# IRCHR_CTRL_J002942REVB.net
KiCad netlist of a schematic drawn in EAGLE
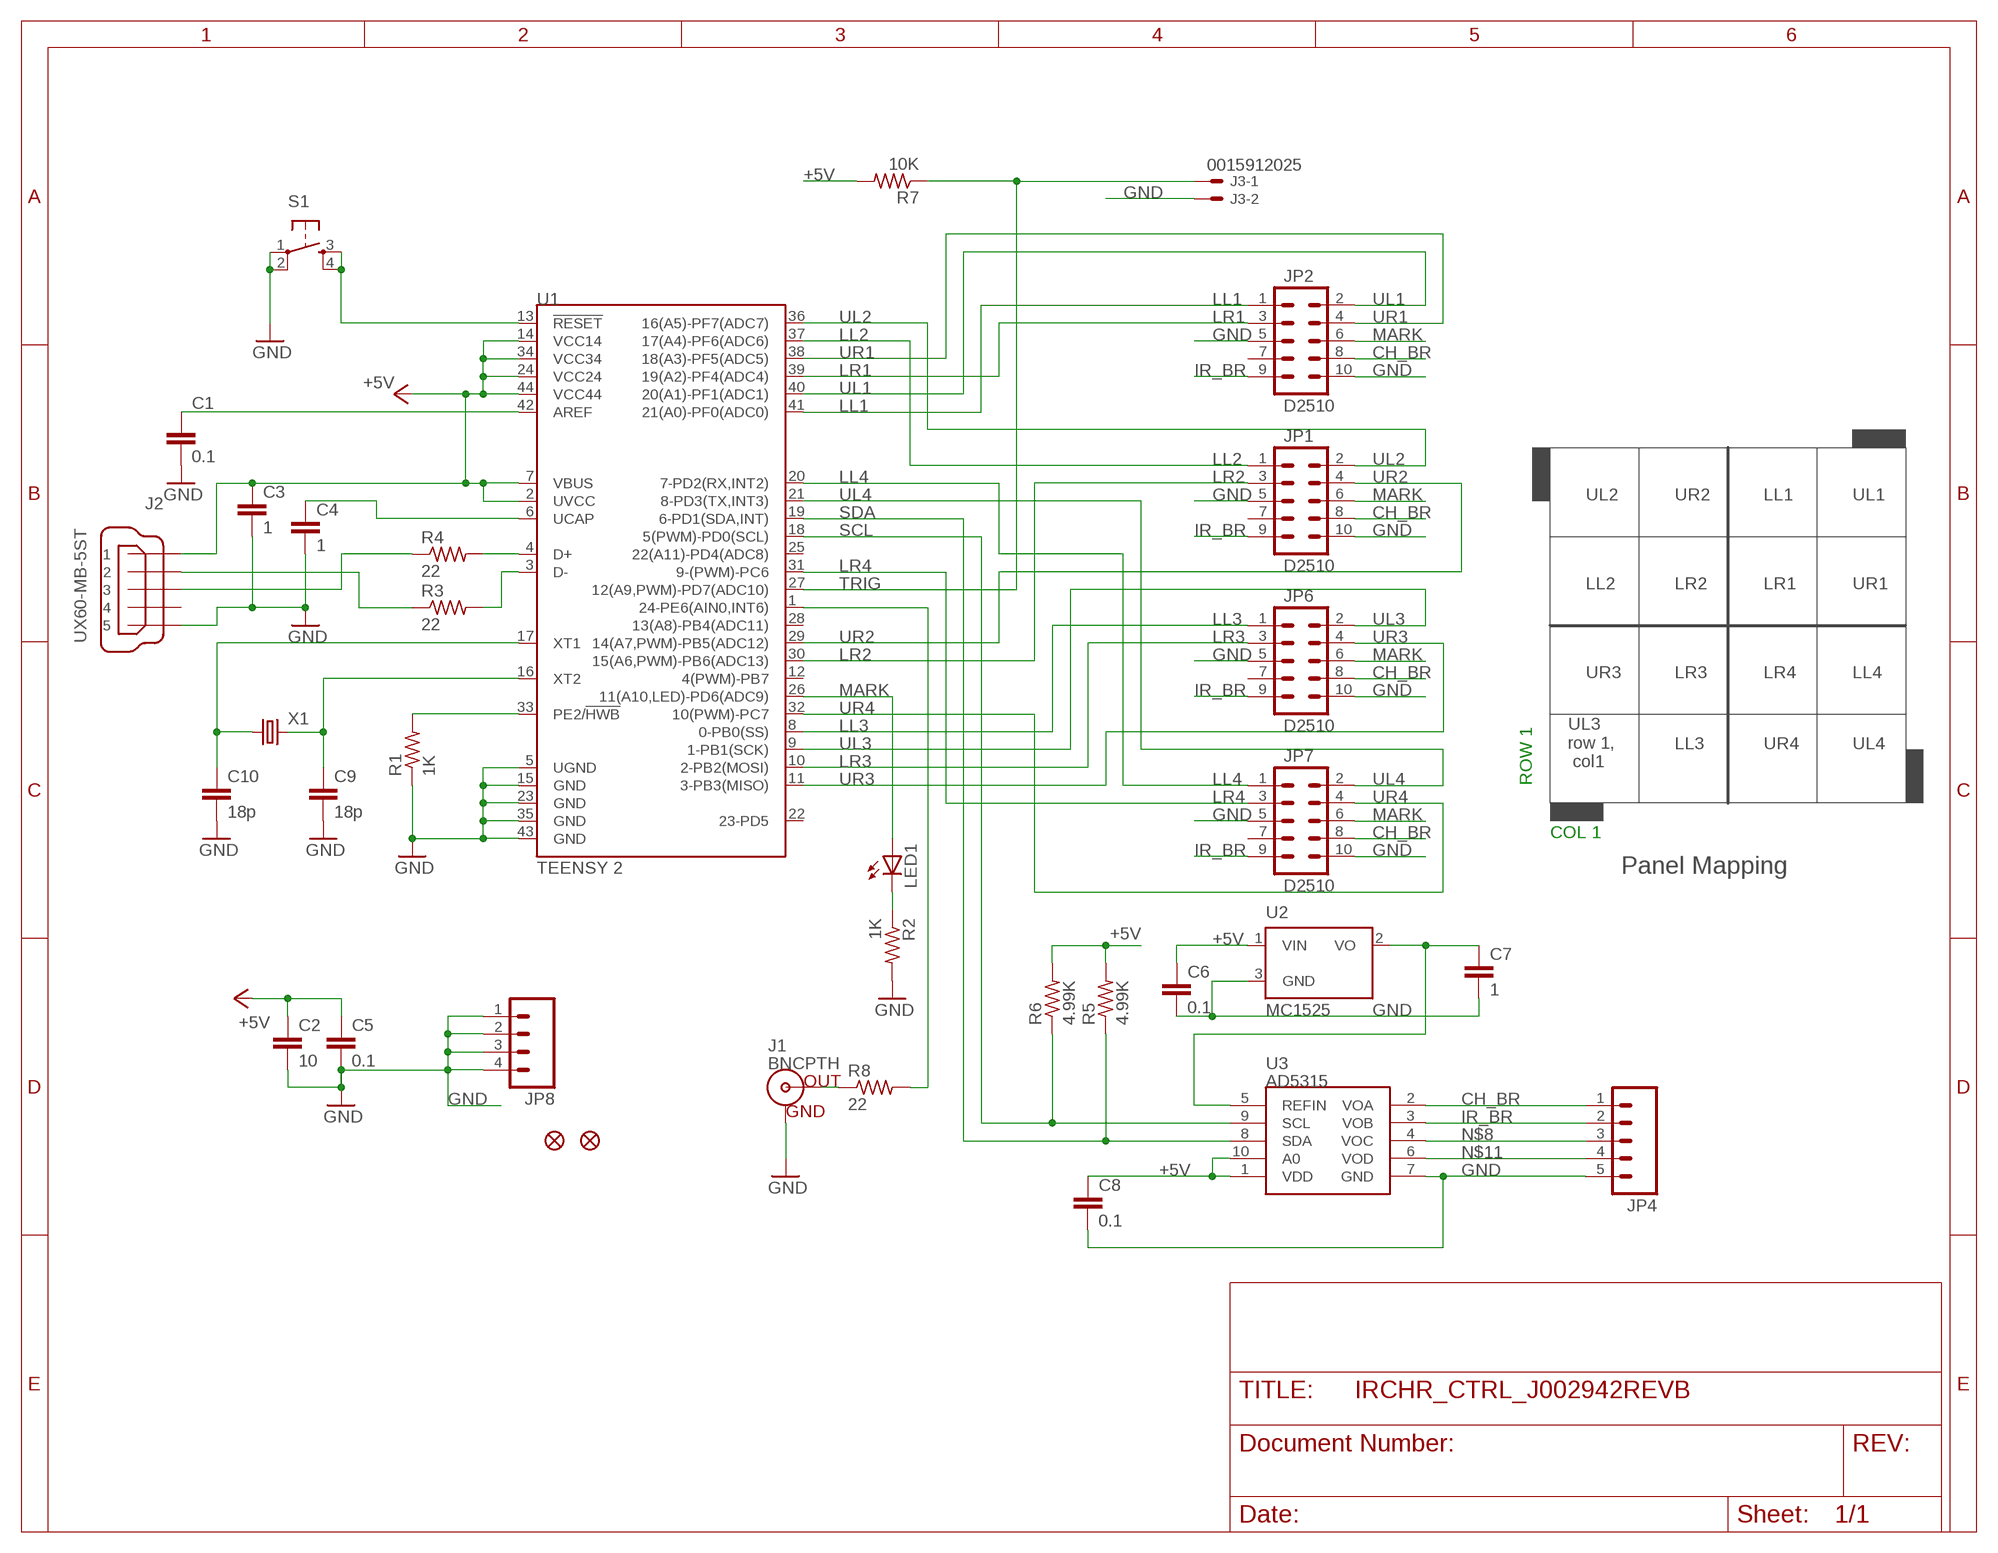
[diagram p0: schematic, sheet 1]

(export (version "E")
  (design (tool "Eeschema 10.0.6"))
  (components
    (comp (ref "C1")
      (value "0.1")
      (footprint "eagle-import:0805S")
      (libsource (lib "eagle-import") (part "STEVES_BU_CAPS0805S"))
    )
    (comp (ref "C2")
      (value "10")
      (footprint "eagle-import:1206S")
      (libsource (lib "eagle-import") (part "CAPS1206S"))
    )
    (comp (ref "C3")
      (value "1")
      (footprint "eagle-import:0805S")
      (libsource (lib "eagle-import") (part "STEVES_BU_CAPS0805S"))
    )
    (comp (ref "C4")
      (value "1")
      (footprint "eagle-import:0805S")
      (libsource (lib "eagle-import") (part "STEVES_BU_CAPS0805S"))
    )
    (comp (ref "C5")
      (value "0.1")
      (footprint "eagle-import:0805S")
      (libsource (lib "eagle-import") (part "STEVES_BU_CAPS0805S"))
    )
    (comp (ref "C6")
      (value "0.1")
      (footprint "eagle-import:0805S")
      (libsource (lib "eagle-import") (part "STEVES_BU_CAPS0805S"))
    )
    (comp (ref "C7")
      (value "1")
      (footprint "eagle-import:0805S")
      (libsource (lib "eagle-import") (part "STEVES_BU_CAPS0805S"))
    )
    (comp (ref "C8")
      (value "0.1")
      (footprint "eagle-import:0805S")
      (libsource (lib "eagle-import") (part "STEVES_BU_CAPS0805S"))
    )
    (comp (ref "C9")
      (value "18p")
      (footprint "eagle-import:0805S")
      (libsource (lib "eagle-import") (part "STEVES_BU_CAPS0805S"))
    )
    (comp (ref "C10")
      (value "18p")
      (footprint "eagle-import:0805S")
      (libsource (lib "eagle-import") (part "STEVES_BU_CAPS0805S"))
    )
    (comp (ref "J1")
      (value "BNCPTH")
      (footprint "eagle-import:BNC")
      (libsource (lib "eagle-import") (part "BNCPTH"))
    )
    (comp (ref "J2")
      (value "UX60-MB-5ST")
      (footprint "eagle-import:UX60-MB-5ST")
      (libsource (lib "eagle-import") (part "MINI-USB-UX60-MB-5ST"))
    )
    (comp (ref "J3")
      (value "0015912025")
      (footprint "eagle-import:15-91-02")
      (libsource (lib "eagle-import") (part "C-GRID-02-15-19"))
    )
    (comp (ref "JP1")
      (value "D2510")
      (footprint "eagle-import:2X5-SHROUDED_SMD_3M")
      (libsource (lib "eagle-import") (part "M05X22X5_SM_3M"))
    )
    (comp (ref "JP2")
      (value "D2510")
      (footprint "eagle-import:2X5-SHROUDED_SMD_3M")
      (libsource (lib "eagle-import") (part "M05X22X5_SM_3M"))
    )
    (comp (ref "JP3")
      (value "FIDUCIAL1X2.5")
      (footprint "eagle-import:FIDUCIAL-1X2.5")
      (libsource (lib "eagle-import") (part "FIDUCIAL1X2.5"))
    )
    (comp (ref "JP4")
      (value "M05LOCK")
      (footprint "eagle-import:1X05_LOCK")
      (libsource (lib "eagle-import") (part "M05LOCK"))
    )
    (comp (ref "JP5")
      (value "FIDUCIAL1X2.5")
      (footprint "eagle-import:FIDUCIAL-1X2.5")
      (libsource (lib "eagle-import") (part "FIDUCIAL1X2.5"))
    )
    (comp (ref "JP6")
      (value "D2510")
      (footprint "eagle-import:2X5-SHROUDED_SMD_3M")
      (libsource (lib "eagle-import") (part "M05X22X5_SM_3M"))
    )
    (comp (ref "JP7")
      (value "D2510")
      (footprint "eagle-import:2X5-SHROUDED_SMD_3M")
      (libsource (lib "eagle-import") (part "M05X22X5_SM_3M"))
    )
    (comp (ref "JP8")
      (value "M04LOCK")
      (footprint "eagle-import:1X04_LOCK")
      (libsource (lib "eagle-import") (part "M04LOCK"))
    )
    (comp (ref "LED1")
      (value "LEDCHIP-LED0805")
      (footprint "eagle-import:CHIP-LED0805")
      (libsource (lib "eagle-import") (part "LEDCHIP-LED0805"))
    )
    (comp (ref "R1")
      (value "1K")
      (footprint "eagle-import:0805S")
      (libsource (lib "eagle-import") (part "RESISTOR_SM0805S"))
    )
    (comp (ref "R2")
      (value "1K")
      (footprint "eagle-import:0805S")
      (libsource (lib "eagle-import") (part "RESISTOR_SM0805S"))
    )
    (comp (ref "R3")
      (value "22")
      (footprint "eagle-import:0805S")
      (libsource (lib "eagle-import") (part "RESISTOR_SM0805S"))
    )
    (comp (ref "R4")
      (value "22")
      (footprint "eagle-import:0805S")
      (libsource (lib "eagle-import") (part "RESISTOR_SM0805S"))
    )
    (comp (ref "R5")
      (value "4.99K")
      (footprint "eagle-import:0805S")
      (libsource (lib "eagle-import") (part "RESISTOR_SM0805S"))
    )
    (comp (ref "R6")
      (value "4.99K")
      (footprint "eagle-import:0805S")
      (libsource (lib "eagle-import") (part "RESISTOR_SM0805S"))
    )
    (comp (ref "R7")
      (value "10K")
      (footprint "eagle-import:0805S")
      (libsource (lib "eagle-import") (part "RESISTOR_SM0805S"))
    )
    (comp (ref "R8")
      (value "22")
      (footprint "eagle-import:0805S")
      (libsource (lib "eagle-import") (part "RESISTOR_SM0805S"))
    )
    (comp (ref "S1")
      (value "TAC_SWITCHSMD")
      (footprint "eagle-import:TACTILE_SWITCH_SMD")
      (libsource (lib "eagle-import") (part "TAC_SWITCHSMD"))
    )
    (comp (ref "U1")
      (value "TEENSY 2")
      (footprint "eagle-import:SPARKFUN-DIGITALIC_TQFP44")
      (libsource (lib "eagle-import") (part "TEENSY_CHIP"))
    )
    (comp (ref "U2")
      (value "MC1525")
      (footprint "eagle-import:SOT23")
      (libsource (lib "eagle-import") (part "MC15TT25"))
    )
    (comp (ref "U3")
      (value "AD5315")
      (footprint "eagle-import:MSOP10")
      (libsource (lib "eagle-import") (part "DAC_AD53X5"))
    )
    (comp (ref "X1")
      (value "CRYSTALCTS406")
      (footprint "eagle-import:CTS406")
      (libsource (lib "eagle-import") (part "CRYSTALCTS406"))
    )
  )
  (nets
    (net (code "1") (name "+5V") (class "Default")
      (node (ref "C2") (pin "1") (pinfunction "1_1") (pintype "passive"))
      (node (ref "C3") (pin "1") (pinfunction "1_1") (pintype "passive"))
      (node (ref "C5") (pin "1") (pinfunction "1_1") (pintype "passive"))
      (node (ref "C6") (pin "1") (pinfunction "1_1") (pintype "passive"))
      (node (ref "C8") (pin "1") (pinfunction "1_1") (pintype "passive"))
      (node (ref "J2") (pin "1") (pinfunction "1_1") (pintype "passive"))
      (node (ref "R5") (pin "2") (pinfunction "2_2") (pintype "passive"))
      (node (ref "R6") (pin "2") (pinfunction "2_2") (pintype "passive"))
      (node (ref "R7") (pin "2") (pinfunction "2_2") (pintype "passive"))
      (node (ref "U1") (pin "14") (pinfunction "VCC14_14") (pintype "bidirectional"))
      (node (ref "U1") (pin "2") (pinfunction "UVCC_2") (pintype "bidirectional"))
      (node (ref "U1") (pin "24") (pinfunction "VCC24_24") (pintype "bidirectional"))
      (node (ref "U1") (pin "34") (pinfunction "VCC34_34") (pintype "bidirectional"))
      (node (ref "U1") (pin "44") (pinfunction "VCC44_44") (pintype "bidirectional"))
      (node (ref "U1") (pin "7") (pinfunction "VBUS_7") (pintype "bidirectional"))
      (node (ref "U2") (pin "1") (pinfunction "VIN_1") (pintype "input"))
      (node (ref "U3") (pin "1") (pinfunction "VDD_1") (pintype "bidirectional"))
      (node (ref "U3") (pin "10") (pinfunction "A0_10") (pintype "bidirectional"))
    )
    (net (code "2") (name "/CH_BR") (class "Default")
      (node (ref "JP1") (pin "8") (pinfunction "8_8") (pintype "passive"))
      (node (ref "JP2") (pin "8") (pinfunction "8_8") (pintype "passive"))
      (node (ref "JP4") (pin "1") (pinfunction "1_1") (pintype "passive"))
      (node (ref "JP6") (pin "8") (pinfunction "8_8") (pintype "passive"))
      (node (ref "JP7") (pin "8") (pinfunction "8_8") (pintype "passive"))
      (node (ref "U3") (pin "2") (pinfunction "VOA_2") (pintype "bidirectional"))
    )
    (net (code "3") (name "/IR_BR") (class "Default")
      (node (ref "JP1") (pin "9") (pinfunction "9_9") (pintype "passive"))
      (node (ref "JP2") (pin "9") (pinfunction "9_9") (pintype "passive"))
      (node (ref "JP4") (pin "2") (pinfunction "2_2") (pintype "passive"))
      (node (ref "JP6") (pin "9") (pinfunction "9_9") (pintype "passive"))
      (node (ref "JP7") (pin "9") (pinfunction "9_9") (pintype "passive"))
      (node (ref "U3") (pin "3") (pinfunction "VOB_3") (pintype "bidirectional"))
    )
    (net (code "4") (name "/LL1") (class "Default")
      (node (ref "JP2") (pin "1") (pinfunction "1_1") (pintype "passive"))
      (node (ref "U1") (pin "41") (pinfunction "21(A0)-PF0(ADC0)_41") (pintype "bidirectional"))
    )
    (net (code "5") (name "/LL2") (class "Default")
      (node (ref "JP1") (pin "1") (pinfunction "1_1") (pintype "passive"))
      (node (ref "U1") (pin "37") (pinfunction "17(A4)-PF6(ADC6)_37") (pintype "bidirectional"))
    )
    (net (code "6") (name "/LL3") (class "Default")
      (node (ref "JP6") (pin "1") (pinfunction "1_1") (pintype "passive"))
      (node (ref "U1") (pin "8") (pinfunction "0-PB0(SS)_8") (pintype "bidirectional"))
    )
    (net (code "7") (name "/LL4") (class "Default")
      (node (ref "JP7") (pin "1") (pinfunction "1_1") (pintype "passive"))
      (node (ref "U1") (pin "20") (pinfunction "7-PD2(RX,INT2)_20") (pintype "bidirectional"))
    )
    (net (code "8") (name "/LR1") (class "Default")
      (node (ref "JP2") (pin "3") (pinfunction "3_3") (pintype "passive"))
      (node (ref "U1") (pin "39") (pinfunction "19(A2)-PF4(ADC4)_39") (pintype "bidirectional"))
    )
    (net (code "9") (name "/LR2") (class "Default")
      (node (ref "JP1") (pin "3") (pinfunction "3_3") (pintype "passive"))
      (node (ref "U1") (pin "30") (pinfunction "15(A6,PWM)-PB6(ADC13)_30") (pintype "bidirectional"))
    )
    (net (code "10") (name "/LR3") (class "Default")
      (node (ref "JP6") (pin "3") (pinfunction "3_3") (pintype "passive"))
      (node (ref "U1") (pin "10") (pinfunction "2-PB2(MOSI)_10") (pintype "bidirectional"))
    )
    (net (code "11") (name "/LR4") (class "Default")
      (node (ref "JP7") (pin "3") (pinfunction "3_3") (pintype "passive"))
      (node (ref "U1") (pin "31") (pinfunction "9-(PWM)-PC6_31") (pintype "bidirectional"))
    )
    (net (code "12") (name "/MARK") (class "Default")
      (node (ref "JP1") (pin "6") (pinfunction "6_6") (pintype "passive"))
      (node (ref "JP2") (pin "6") (pinfunction "6_6") (pintype "passive"))
      (node (ref "JP6") (pin "6") (pinfunction "6_6") (pintype "passive"))
      (node (ref "JP7") (pin "6") (pinfunction "6_6") (pintype "passive"))
      (node (ref "LED1") (pin "A") (pinfunction "A_A") (pintype "passive"))
      (node (ref "U1") (pin "26") (pinfunction "11(A10,LED)-PD6(ADC9)_26") (pintype "bidirectional"))
    )
    (net (code "13") (name "/N$8") (class "Default")
      (node (ref "JP4") (pin "3") (pinfunction "3_3") (pintype "passive"))
      (node (ref "U3") (pin "4") (pinfunction "VOC_4") (pintype "bidirectional"))
    )
    (net (code "14") (name "/N$11") (class "Default")
      (node (ref "JP4") (pin "4") (pinfunction "4_4") (pintype "passive"))
      (node (ref "U3") (pin "6") (pinfunction "VOD_6") (pintype "bidirectional"))
    )
    (net (code "15") (name "/SCL") (class "Default")
      (node (ref "R6") (pin "1") (pinfunction "1_1") (pintype "passive"))
      (node (ref "U1") (pin "18") (pinfunction "5(PWM)-PD0(SCL)_18") (pintype "bidirectional"))
      (node (ref "U3") (pin "9") (pinfunction "SCL_9") (pintype "bidirectional"))
    )
    (net (code "16") (name "/SDA") (class "Default")
      (node (ref "R5") (pin "1") (pinfunction "1_1") (pintype "passive"))
      (node (ref "U1") (pin "19") (pinfunction "6-PD1(SDA,INT)_19") (pintype "bidirectional"))
      (node (ref "U3") (pin "8") (pinfunction "SDA_8") (pintype "bidirectional"))
    )
    (net (code "17") (name "/TRIG") (class "Default")
      (node (ref "J3") (pin "1") (pinfunction "S_1") (pintype "passive"))
      (node (ref "R7") (pin "1") (pinfunction "1_1") (pintype "passive"))
      (node (ref "U1") (pin "27") (pinfunction "12(A9,PWM)-PD7(ADC10)_27") (pintype "bidirectional"))
    )
    (net (code "18") (name "/UL1") (class "Default")
      (node (ref "JP2") (pin "2") (pinfunction "2_2") (pintype "passive"))
      (node (ref "U1") (pin "40") (pinfunction "20(A1)-PF1(ADC1)_40") (pintype "bidirectional"))
    )
    (net (code "19") (name "/UL2") (class "Default")
      (node (ref "JP1") (pin "2") (pinfunction "2_2") (pintype "passive"))
      (node (ref "U1") (pin "36") (pinfunction "16(A5)-PF7(ADC7)_36") (pintype "bidirectional"))
    )
    (net (code "20") (name "/UL3") (class "Default")
      (node (ref "JP6") (pin "2") (pinfunction "2_2") (pintype "passive"))
      (node (ref "U1") (pin "9") (pinfunction "1-PB1(SCK)_9") (pintype "bidirectional"))
    )
    (net (code "21") (name "/UL4") (class "Default")
      (node (ref "JP7") (pin "2") (pinfunction "2_2") (pintype "passive"))
      (node (ref "U1") (pin "21") (pinfunction "8-PD3(TX,INT3)_21") (pintype "bidirectional"))
    )
    (net (code "22") (name "/UR1") (class "Default")
      (node (ref "JP2") (pin "4") (pinfunction "4_4") (pintype "passive"))
      (node (ref "U1") (pin "38") (pinfunction "18(A3)-PF5(ADC5)_38") (pintype "bidirectional"))
    )
    (net (code "23") (name "/UR2") (class "Default")
      (node (ref "JP1") (pin "4") (pinfunction "4_4") (pintype "passive"))
      (node (ref "U1") (pin "29") (pinfunction "14(A7,PWM)-PB5(ADC12)_29") (pintype "bidirectional"))
    )
    (net (code "24") (name "/UR3") (class "Default")
      (node (ref "JP6") (pin "4") (pinfunction "4_4") (pintype "passive"))
      (node (ref "U1") (pin "11") (pinfunction "3-PB3(MISO)_11") (pintype "bidirectional"))
    )
    (net (code "25") (name "/UR4") (class "Default")
      (node (ref "JP7") (pin "4") (pinfunction "4_4") (pintype "passive"))
      (node (ref "U1") (pin "32") (pinfunction "10(PWM)-PC7_32") (pintype "bidirectional"))
    )
    (net (code "26") (name "GND") (class "Default")
      (node (ref "C1") (pin "2") (pinfunction "2_2") (pintype "passive"))
      (node (ref "C10") (pin "2") (pinfunction "2_2") (pintype "passive"))
      (node (ref "C2") (pin "2") (pinfunction "2_2") (pintype "passive"))
      (node (ref "C3") (pin "2") (pinfunction "2_2") (pintype "passive"))
      (node (ref "C4") (pin "2") (pinfunction "2_2") (pintype "passive"))
      (node (ref "C5") (pin "2") (pinfunction "2_2") (pintype "passive"))
      (node (ref "C6") (pin "2") (pinfunction "2_2") (pintype "passive"))
      (node (ref "C7") (pin "2") (pinfunction "2_2") (pintype "passive"))
      (node (ref "C8") (pin "2") (pinfunction "2_2") (pintype "passive"))
      (node (ref "C9") (pin "2") (pinfunction "2_2") (pintype "passive"))
      (node (ref "J1") (pin "GND") (pinfunction "GND_GND") (pintype "bidirectional"))
      (node (ref "J2") (pin "5") (pinfunction "5_5") (pintype "passive"))
      (node (ref "J3") (pin "2") (pinfunction "S_2") (pintype "passive"))
      (node (ref "JP1") (pin "10") (pinfunction "10_10") (pintype "passive"))
      (node (ref "JP1") (pin "5") (pinfunction "5_5") (pintype "passive"))
      (node (ref "JP2") (pin "10") (pinfunction "10_10") (pintype "passive"))
      (node (ref "JP2") (pin "5") (pinfunction "5_5") (pintype "passive"))
      (node (ref "JP4") (pin "5") (pinfunction "5_5") (pintype "passive"))
      (node (ref "JP6") (pin "10") (pinfunction "10_10") (pintype "passive"))
      (node (ref "JP6") (pin "5") (pinfunction "5_5") (pintype "passive"))
      (node (ref "JP7") (pin "10") (pinfunction "10_10") (pintype "passive"))
      (node (ref "JP7") (pin "5") (pinfunction "5_5") (pintype "passive"))
      (node (ref "JP8") (pin "1") (pinfunction "1_1") (pintype "passive"))
      (node (ref "JP8") (pin "2") (pinfunction "2_2") (pintype "passive"))
      (node (ref "JP8") (pin "3") (pinfunction "3_3") (pintype "passive"))
      (node (ref "JP8") (pin "4") (pinfunction "4_4") (pintype "passive"))
      (node (ref "R1") (pin "1") (pinfunction "1_1") (pintype "passive"))
      (node (ref "R2") (pin "2") (pinfunction "2_2") (pintype "passive"))
      (node (ref "S1") (pin "1") (pinfunction "1_1") (pintype "passive"))
      (node (ref "S1") (pin "2") (pinfunction "2_2") (pintype "passive"))
      (node (ref "U1") (pin "15") (pinfunction "GND_15") (pintype "bidirectional"))
      (node (ref "U1") (pin "23") (pinfunction "GND_23") (pintype "bidirectional"))
      (node (ref "U1") (pin "35") (pinfunction "GND_35") (pintype "bidirectional"))
      (node (ref "U1") (pin "43") (pinfunction "GND_43") (pintype "bidirectional"))
      (node (ref "U1") (pin "5") (pinfunction "UGND_5") (pintype "bidirectional"))
      (node (ref "U2") (pin "3") (pinfunction "GND_3") (pintype "passive"))
      (node (ref "U3") (pin "7") (pinfunction "GND_7") (pintype "bidirectional"))
    )
    (net (code "27") (name "Net-(J1-OUT)") (class "Default")
      (node (ref "J1") (pin "S") (pinfunction "OUT_S") (pintype "bidirectional"))
      (node (ref "R8") (pin "1") (pinfunction "1_1") (pintype "passive"))
    )
    (net (code "28") (name "Net-(J2-Pad2)") (class "Default")
      (node (ref "J2") (pin "2") (pinfunction "2_2") (pintype "passive"))
      (node (ref "R3") (pin "1") (pinfunction "1_1") (pintype "passive"))
    )
    (net (code "29") (name "Net-(J2-Pad3)") (class "Default")
      (node (ref "J2") (pin "3") (pinfunction "3_3") (pintype "passive"))
      (node (ref "R4") (pin "1") (pinfunction "1_1") (pintype "passive"))
    )
    (net (code "30") (name "Net-(LED1-PadC)") (class "Default")
      (node (ref "LED1") (pin "C") (pinfunction "C_C") (pintype "passive"))
      (node (ref "R2") (pin "1") (pinfunction "1_1") (pintype "passive"))
    )
    (net (code "31") (name "Net-(U1-24-PE6(AIN0,INT6))") (class "Default")
      (node (ref "R8") (pin "2") (pinfunction "2_2") (pintype "passive"))
      (node (ref "U1") (pin "1") (pinfunction "24-PE6(AIN0,INT6)_1") (pintype "bidirectional"))
    )
    (net (code "32") (name "Net-(U1-AREF)") (class "Default")
      (node (ref "C1") (pin "1") (pinfunction "1_1") (pintype "passive"))
      (node (ref "U1") (pin "42") (pinfunction "AREF_42") (pintype "bidirectional"))
    )
    (net (code "33") (name "Net-(U1-D+)") (class "Default")
      (node (ref "R4") (pin "2") (pinfunction "2_2") (pintype "passive"))
      (node (ref "U1") (pin "4") (pinfunction "D+_4") (pintype "bidirectional"))
    )
    (net (code "34") (name "Net-(U1-D-)") (class "Default")
      (node (ref "R3") (pin "2") (pinfunction "2_2") (pintype "passive"))
      (node (ref "U1") (pin "3") (pinfunction "D-_3") (pintype "bidirectional"))
    )
    (net (code "35") (name "Net-(U1-PE2{slash}~{HWB})") (class "Default")
      (node (ref "R1") (pin "2") (pinfunction "2_2") (pintype "passive"))
      (node (ref "U1") (pin "33") (pinfunction "PE2/~{HWB}_33") (pintype "bidirectional"))
    )
    (net (code "36") (name "Net-(U1-UCAP)") (class "Default")
      (node (ref "C4") (pin "1") (pinfunction "1_1") (pintype "passive"))
      (node (ref "U1") (pin "6") (pinfunction "UCAP_6") (pintype "bidirectional"))
    )
    (net (code "37") (name "Net-(U1-XT1)") (class "Default")
      (node (ref "C10") (pin "1") (pinfunction "1_1") (pintype "passive"))
      (node (ref "U1") (pin "17") (pinfunction "XT1_17") (pintype "bidirectional"))
      (node (ref "X1") (pin "1") (pinfunction "1_1") (pintype "passive"))
    )
    (net (code "38") (name "Net-(U1-XT2)") (class "Default")
      (node (ref "C9") (pin "1") (pinfunction "1_1") (pintype "passive"))
      (node (ref "U1") (pin "16") (pinfunction "XT2_16") (pintype "bidirectional"))
      (node (ref "X1") (pin "3") (pinfunction "2_3") (pintype "passive"))
    )
    (net (code "39") (name "Net-(U1-~{RESET})") (class "Default")
      (node (ref "S1") (pin "3") (pinfunction "3_3") (pintype "passive"))
      (node (ref "S1") (pin "4") (pinfunction "4_4") (pintype "passive"))
      (node (ref "U1") (pin "13") (pinfunction "~{RESET}_13") (pintype "bidirectional"))
    )
    (net (code "40") (name "Net-(U2-VO)") (class "Default")
      (node (ref "C7") (pin "1") (pinfunction "1_1") (pintype "passive"))
      (node (ref "U2") (pin "2") (pinfunction "VO_2") (pintype "output"))
      (node (ref "U3") (pin "5") (pinfunction "REFIN_5") (pintype "bidirectional"))
    )
    (net (code "41") (name "unconnected-(J2-Pad4)") (class "Default")
      (node (ref "J2") (pin "4") (pinfunction "4_4") (pintype "passive"))
    )
    (net (code "42") (name "unconnected-(JP1-Pad7)") (class "Default")
      (node (ref "JP1") (pin "7") (pinfunction "7_7") (pintype "passive"))
    )
    (net (code "43") (name "unconnected-(JP2-Pad7)") (class "Default")
      (node (ref "JP2") (pin "7") (pinfunction "7_7") (pintype "passive"))
    )
    (net (code "44") (name "unconnected-(JP6-Pad7)") (class "Default")
      (node (ref "JP6") (pin "7") (pinfunction "7_7") (pintype "passive"))
    )
    (net (code "45") (name "unconnected-(JP7-Pad7)") (class "Default")
      (node (ref "JP7") (pin "7") (pinfunction "7_7") (pintype "passive"))
    )
    (net (code "46") (name "unconnected-(U1-4(PWM)-PB7-Pad12)") (class "Default")
      (node (ref "U1") (pin "12") (pinfunction "4(PWM)-PB7_12") (pintype "bidirectional"))
    )
    (net (code "47") (name "unconnected-(U1-13(A8)-PB4(ADC11)-Pad28)") (class "Default")
      (node (ref "U1") (pin "28") (pinfunction "13(A8)-PB4(ADC11)_28") (pintype "bidirectional"))
    )
    (net (code "48") (name "unconnected-(U1-22(A11)-PD4(ADC8)-Pad25)") (class "Default")
      (node (ref "U1") (pin "25") (pinfunction "22(A11)-PD4(ADC8)_25") (pintype "bidirectional"))
    )
    (net (code "49") (name "unconnected-(U1-23-PD5-Pad22)") (class "Default")
      (node (ref "U1") (pin "22") (pinfunction "23-PD5_22") (pintype "bidirectional"))
    )
  )
)
